# connector-top-j3-1.net
KiCad netlist of a schematic drawn in Altium Designer
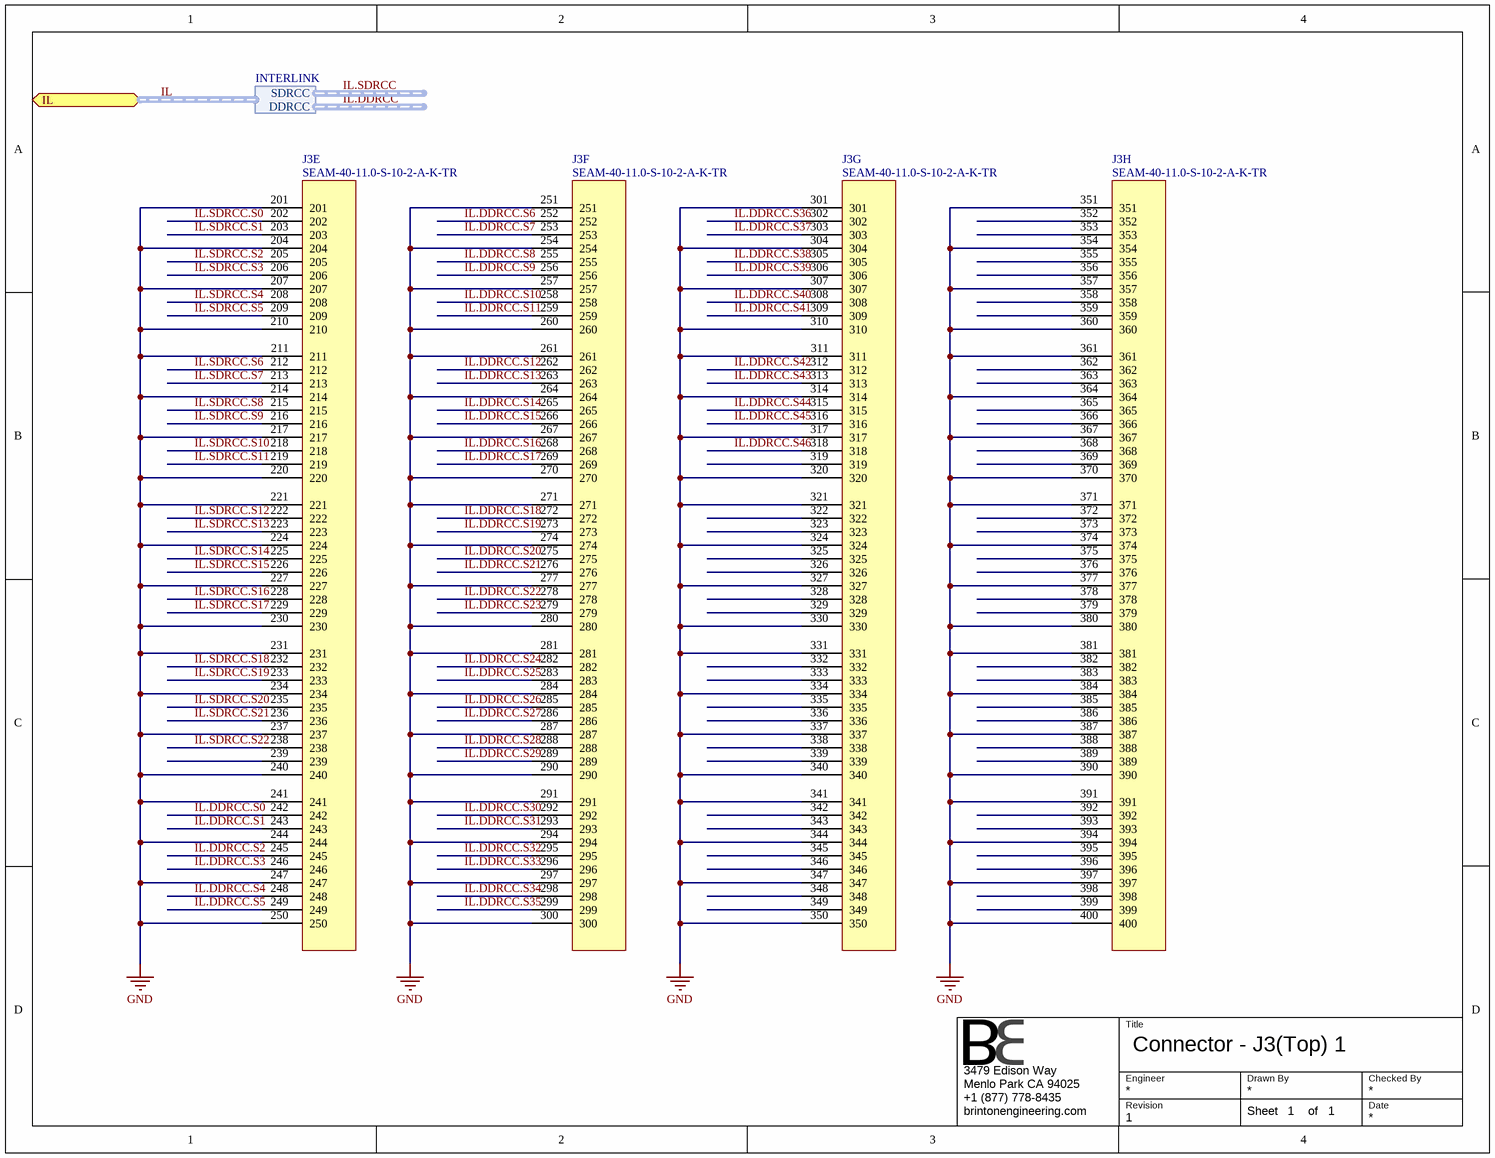
[diagram p0: connector-top-j3-1.SchDoc]

(export (version "E")
  (design (tool "Eeschema 10.0.6"))
  (components
    (comp (ref "J3")
      (value "SEAM-40-11.0-S-10-2-A-K-TR")
      (footprint "samtec:SEAM-40-11.0-S-10-2-A-K-TR")
      (description "Terminal Array Assembly, Surface Mount, 0.050\" Pitch, 400 Pins")
      (fields (field (name "MANUFACTURER") "Samtec"))
      (libsource (lib "samtec") (part "SEAM-40-11.0-S-10-2-A-K-TR"))
    )
  )
  (nets
    (net (code "3") (name "/IL.DDRCC.S0") (class "Default")
      (node (ref "J3") (pin "242") (pinfunction "242_242") (pintype "passive"))
    )
    (net (code "4") (name "/IL.DDRCC.S1") (class "Default")
      (node (ref "J3") (pin "243") (pinfunction "243_243") (pintype "passive"))
    )
    (net (code "5") (name "/IL.DDRCC.S2") (class "Default")
      (node (ref "J3") (pin "245") (pinfunction "245_245") (pintype "passive"))
    )
    (net (code "6") (name "/IL.DDRCC.S3") (class "Default")
      (node (ref "J3") (pin "246") (pinfunction "246_246") (pintype "passive"))
    )
    (net (code "7") (name "/IL.DDRCC.S4") (class "Default")
      (node (ref "J3") (pin "248") (pinfunction "248_248") (pintype "passive"))
    )
    (net (code "8") (name "/IL.DDRCC.S5") (class "Default")
      (node (ref "J3") (pin "249") (pinfunction "249_249") (pintype "passive"))
    )
    (net (code "9") (name "/IL.DDRCC.S6") (class "Default")
      (node (ref "J3") (pin "252") (pinfunction "252_252") (pintype "passive"))
    )
    (net (code "10") (name "/IL.DDRCC.S7") (class "Default")
      (node (ref "J3") (pin "253") (pinfunction "253_253") (pintype "passive"))
    )
    (net (code "11") (name "/IL.DDRCC.S8") (class "Default")
      (node (ref "J3") (pin "255") (pinfunction "255_255") (pintype "passive"))
    )
    (net (code "12") (name "/IL.DDRCC.S9") (class "Default")
      (node (ref "J3") (pin "256") (pinfunction "256_256") (pintype "passive"))
    )
    (net (code "13") (name "/IL.DDRCC.S10") (class "Default")
      (node (ref "J3") (pin "258") (pinfunction "258_258") (pintype "passive"))
    )
    (net (code "14") (name "/IL.DDRCC.S11") (class "Default")
      (node (ref "J3") (pin "259") (pinfunction "259_259") (pintype "passive"))
    )
    (net (code "15") (name "/IL.DDRCC.S12") (class "Default")
      (node (ref "J3") (pin "262") (pinfunction "262_262") (pintype "passive"))
    )
    (net (code "16") (name "/IL.DDRCC.S13") (class "Default")
      (node (ref "J3") (pin "263") (pinfunction "263_263") (pintype "passive"))
    )
    (net (code "17") (name "/IL.DDRCC.S14") (class "Default")
      (node (ref "J3") (pin "265") (pinfunction "265_265") (pintype "passive"))
    )
    (net (code "18") (name "/IL.DDRCC.S15") (class "Default")
      (node (ref "J3") (pin "266") (pinfunction "266_266") (pintype "passive"))
    )
    (net (code "19") (name "/IL.DDRCC.S16") (class "Default")
      (node (ref "J3") (pin "268") (pinfunction "268_268") (pintype "passive"))
    )
    (net (code "20") (name "/IL.DDRCC.S17") (class "Default")
      (node (ref "J3") (pin "269") (pinfunction "269_269") (pintype "passive"))
    )
    (net (code "21") (name "/IL.DDRCC.S18") (class "Default")
      (node (ref "J3") (pin "272") (pinfunction "272_272") (pintype "passive"))
    )
    (net (code "22") (name "/IL.DDRCC.S19") (class "Default")
      (node (ref "J3") (pin "273") (pinfunction "273_273") (pintype "passive"))
    )
    (net (code "23") (name "/IL.DDRCC.S20") (class "Default")
      (node (ref "J3") (pin "275") (pinfunction "275_275") (pintype "passive"))
    )
    (net (code "24") (name "/IL.DDRCC.S21") (class "Default")
      (node (ref "J3") (pin "276") (pinfunction "276_276") (pintype "passive"))
    )
    (net (code "25") (name "/IL.DDRCC.S22") (class "Default")
      (node (ref "J3") (pin "278") (pinfunction "278_278") (pintype "passive"))
    )
    (net (code "26") (name "/IL.DDRCC.S23") (class "Default")
      (node (ref "J3") (pin "279") (pinfunction "279_279") (pintype "passive"))
    )
    (net (code "27") (name "/IL.DDRCC.S24") (class "Default")
      (node (ref "J3") (pin "282") (pinfunction "282_282") (pintype "passive"))
    )
    (net (code "28") (name "/IL.DDRCC.S25") (class "Default")
      (node (ref "J3") (pin "283") (pinfunction "283_283") (pintype "passive"))
    )
    (net (code "29") (name "/IL.DDRCC.S26") (class "Default")
      (node (ref "J3") (pin "285") (pinfunction "285_285") (pintype "passive"))
    )
    (net (code "30") (name "/IL.DDRCC.S27") (class "Default")
      (node (ref "J3") (pin "286") (pinfunction "286_286") (pintype "passive"))
    )
    (net (code "31") (name "/IL.DDRCC.S28") (class "Default")
      (node (ref "J3") (pin "288") (pinfunction "288_288") (pintype "passive"))
    )
    (net (code "32") (name "/IL.DDRCC.S29") (class "Default")
      (node (ref "J3") (pin "289") (pinfunction "289_289") (pintype "passive"))
    )
    (net (code "33") (name "/IL.DDRCC.S30") (class "Default")
      (node (ref "J3") (pin "292") (pinfunction "292_292") (pintype "passive"))
    )
    (net (code "34") (name "/IL.DDRCC.S31") (class "Default")
      (node (ref "J3") (pin "293") (pinfunction "293_293") (pintype "passive"))
    )
    (net (code "35") (name "/IL.DDRCC.S32") (class "Default")
      (node (ref "J3") (pin "295") (pinfunction "295_295") (pintype "passive"))
    )
    (net (code "36") (name "/IL.DDRCC.S33") (class "Default")
      (node (ref "J3") (pin "296") (pinfunction "296_296") (pintype "passive"))
    )
    (net (code "37") (name "/IL.DDRCC.S34") (class "Default")
      (node (ref "J3") (pin "298") (pinfunction "298_298") (pintype "passive"))
    )
    (net (code "38") (name "/IL.DDRCC.S35") (class "Default")
      (node (ref "J3") (pin "299") (pinfunction "299_299") (pintype "passive"))
    )
    (net (code "39") (name "/IL.DDRCC.S36") (class "Default")
      (node (ref "J3") (pin "302") (pinfunction "302_302") (pintype "passive"))
    )
    (net (code "40") (name "/IL.DDRCC.S37") (class "Default")
      (node (ref "J3") (pin "303") (pinfunction "303_303") (pintype "passive"))
    )
    (net (code "41") (name "/IL.DDRCC.S38") (class "Default")
      (node (ref "J3") (pin "305") (pinfunction "305_305") (pintype "passive"))
    )
    (net (code "42") (name "/IL.DDRCC.S39") (class "Default")
      (node (ref "J3") (pin "306") (pinfunction "306_306") (pintype "passive"))
    )
    (net (code "43") (name "/IL.DDRCC.S40") (class "Default")
      (node (ref "J3") (pin "308") (pinfunction "308_308") (pintype "passive"))
    )
    (net (code "44") (name "/IL.DDRCC.S41") (class "Default")
      (node (ref "J3") (pin "309") (pinfunction "309_309") (pintype "passive"))
    )
    (net (code "45") (name "/IL.DDRCC.S42") (class "Default")
      (node (ref "J3") (pin "312") (pinfunction "312_312") (pintype "passive"))
    )
    (net (code "46") (name "/IL.DDRCC.S43") (class "Default")
      (node (ref "J3") (pin "313") (pinfunction "313_313") (pintype "passive"))
    )
    (net (code "47") (name "/IL.DDRCC.S44") (class "Default")
      (node (ref "J3") (pin "315") (pinfunction "315_315") (pintype "passive"))
    )
    (net (code "48") (name "/IL.DDRCC.S45") (class "Default")
      (node (ref "J3") (pin "316") (pinfunction "316_316") (pintype "passive"))
    )
    (net (code "49") (name "/IL.DDRCC.S46") (class "Default")
      (node (ref "J3") (pin "318") (pinfunction "318_318") (pintype "passive"))
    )
    (net (code "51") (name "/IL.SDRCC.S0") (class "Default")
      (node (ref "J3") (pin "202") (pinfunction "202_202") (pintype "passive"))
    )
    (net (code "52") (name "/IL.SDRCC.S1") (class "Default")
      (node (ref "J3") (pin "203") (pinfunction "203_203") (pintype "passive"))
    )
    (net (code "53") (name "/IL.SDRCC.S2") (class "Default")
      (node (ref "J3") (pin "205") (pinfunction "205_205") (pintype "passive"))
    )
    (net (code "54") (name "/IL.SDRCC.S3") (class "Default")
      (node (ref "J3") (pin "206") (pinfunction "206_206") (pintype "passive"))
    )
    (net (code "55") (name "/IL.SDRCC.S4") (class "Default")
      (node (ref "J3") (pin "208") (pinfunction "208_208") (pintype "passive"))
    )
    (net (code "56") (name "/IL.SDRCC.S5") (class "Default")
      (node (ref "J3") (pin "209") (pinfunction "209_209") (pintype "passive"))
    )
    (net (code "57") (name "/IL.SDRCC.S6") (class "Default")
      (node (ref "J3") (pin "212") (pinfunction "212_212") (pintype "passive"))
    )
    (net (code "58") (name "/IL.SDRCC.S7") (class "Default")
      (node (ref "J3") (pin "213") (pinfunction "213_213") (pintype "passive"))
    )
    (net (code "59") (name "/IL.SDRCC.S8") (class "Default")
      (node (ref "J3") (pin "215") (pinfunction "215_215") (pintype "passive"))
    )
    (net (code "60") (name "/IL.SDRCC.S9") (class "Default")
      (node (ref "J3") (pin "216") (pinfunction "216_216") (pintype "passive"))
    )
    (net (code "61") (name "/IL.SDRCC.S10") (class "Default")
      (node (ref "J3") (pin "218") (pinfunction "218_218") (pintype "passive"))
    )
    (net (code "62") (name "/IL.SDRCC.S11") (class "Default")
      (node (ref "J3") (pin "219") (pinfunction "219_219") (pintype "passive"))
    )
    (net (code "63") (name "/IL.SDRCC.S12") (class "Default")
      (node (ref "J3") (pin "222") (pinfunction "222_222") (pintype "passive"))
    )
    (net (code "64") (name "/IL.SDRCC.S13") (class "Default")
      (node (ref "J3") (pin "223") (pinfunction "223_223") (pintype "passive"))
    )
    (net (code "65") (name "/IL.SDRCC.S14") (class "Default")
      (node (ref "J3") (pin "225") (pinfunction "225_225") (pintype "passive"))
    )
    (net (code "66") (name "/IL.SDRCC.S15") (class "Default")
      (node (ref "J3") (pin "226") (pinfunction "226_226") (pintype "passive"))
    )
    (net (code "67") (name "/IL.SDRCC.S16") (class "Default")
      (node (ref "J3") (pin "228") (pinfunction "228_228") (pintype "passive"))
    )
    (net (code "68") (name "/IL.SDRCC.S17") (class "Default")
      (node (ref "J3") (pin "229") (pinfunction "229_229") (pintype "passive"))
    )
    (net (code "69") (name "/IL.SDRCC.S18") (class "Default")
      (node (ref "J3") (pin "232") (pinfunction "232_232") (pintype "passive"))
    )
    (net (code "70") (name "/IL.SDRCC.S19") (class "Default")
      (node (ref "J3") (pin "233") (pinfunction "233_233") (pintype "passive"))
    )
    (net (code "71") (name "/IL.SDRCC.S20") (class "Default")
      (node (ref "J3") (pin "235") (pinfunction "235_235") (pintype "passive"))
    )
    (net (code "72") (name "/IL.SDRCC.S21") (class "Default")
      (node (ref "J3") (pin "236") (pinfunction "236_236") (pintype "passive"))
    )
    (net (code "73") (name "/IL.SDRCC.S22") (class "Default")
      (node (ref "J3") (pin "238") (pinfunction "238_238") (pintype "passive"))
    )
    (net (code "75") (name "GND") (class "Default")
      (node (ref "J3") (pin "201") (pinfunction "201_201") (pintype "passive"))
      (node (ref "J3") (pin "204") (pinfunction "204_204") (pintype "passive"))
      (node (ref "J3") (pin "207") (pinfunction "207_207") (pintype "passive"))
      (node (ref "J3") (pin "210") (pinfunction "210_210") (pintype "passive"))
      (node (ref "J3") (pin "211") (pinfunction "211_211") (pintype "passive"))
      (node (ref "J3") (pin "214") (pinfunction "214_214") (pintype "passive"))
      (node (ref "J3") (pin "217") (pinfunction "217_217") (pintype "passive"))
      (node (ref "J3") (pin "220") (pinfunction "220_220") (pintype "passive"))
      (node (ref "J3") (pin "221") (pinfunction "221_221") (pintype "passive"))
      (node (ref "J3") (pin "224") (pinfunction "224_224") (pintype "passive"))
      (node (ref "J3") (pin "227") (pinfunction "227_227") (pintype "passive"))
      (node (ref "J3") (pin "230") (pinfunction "230_230") (pintype "passive"))
      (node (ref "J3") (pin "231") (pinfunction "231_231") (pintype "passive"))
      (node (ref "J3") (pin "234") (pinfunction "234_234") (pintype "passive"))
      (node (ref "J3") (pin "237") (pinfunction "237_237") (pintype "passive"))
      (node (ref "J3") (pin "240") (pinfunction "240_240") (pintype "passive"))
      (node (ref "J3") (pin "241") (pinfunction "241_241") (pintype "passive"))
      (node (ref "J3") (pin "244") (pinfunction "244_244") (pintype "passive"))
      (node (ref "J3") (pin "247") (pinfunction "247_247") (pintype "passive"))
      (node (ref "J3") (pin "250") (pinfunction "250_250") (pintype "passive"))
      (node (ref "J3") (pin "251") (pinfunction "251_251") (pintype "passive"))
      (node (ref "J3") (pin "254") (pinfunction "254_254") (pintype "passive"))
      (node (ref "J3") (pin "257") (pinfunction "257_257") (pintype "passive"))
      (node (ref "J3") (pin "260") (pinfunction "260_260") (pintype "passive"))
      (node (ref "J3") (pin "261") (pinfunction "261_261") (pintype "passive"))
      (node (ref "J3") (pin "264") (pinfunction "264_264") (pintype "passive"))
      (node (ref "J3") (pin "267") (pinfunction "267_267") (pintype "passive"))
      (node (ref "J3") (pin "270") (pinfunction "270_270") (pintype "passive"))
      (node (ref "J3") (pin "271") (pinfunction "271_271") (pintype "passive"))
      (node (ref "J3") (pin "274") (pinfunction "274_274") (pintype "passive"))
      (node (ref "J3") (pin "277") (pinfunction "277_277") (pintype "passive"))
      (node (ref "J3") (pin "280") (pinfunction "280_280") (pintype "passive"))
      (node (ref "J3") (pin "281") (pinfunction "281_281") (pintype "passive"))
      (node (ref "J3") (pin "284") (pinfunction "284_284") (pintype "passive"))
      (node (ref "J3") (pin "287") (pinfunction "287_287") (pintype "passive"))
      (node (ref "J3") (pin "290") (pinfunction "290_290") (pintype "passive"))
      (node (ref "J3") (pin "291") (pinfunction "291_291") (pintype "passive"))
      (node (ref "J3") (pin "294") (pinfunction "294_294") (pintype "passive"))
      (node (ref "J3") (pin "297") (pinfunction "297_297") (pintype "passive"))
      (node (ref "J3") (pin "300") (pinfunction "300_300") (pintype "passive"))
      (node (ref "J3") (pin "301") (pinfunction "301_301") (pintype "passive"))
      (node (ref "J3") (pin "304") (pinfunction "304_304") (pintype "passive"))
      (node (ref "J3") (pin "307") (pinfunction "307_307") (pintype "passive"))
      (node (ref "J3") (pin "310") (pinfunction "310_310") (pintype "passive"))
      (node (ref "J3") (pin "311") (pinfunction "311_311") (pintype "passive"))
      (node (ref "J3") (pin "314") (pinfunction "314_314") (pintype "passive"))
      (node (ref "J3") (pin "317") (pinfunction "317_317") (pintype "passive"))
      (node (ref "J3") (pin "320") (pinfunction "320_320") (pintype "passive"))
      (node (ref "J3") (pin "321") (pinfunction "321_321") (pintype "passive"))
      (node (ref "J3") (pin "324") (pinfunction "324_324") (pintype "passive"))
      (node (ref "J3") (pin "327") (pinfunction "327_327") (pintype "passive"))
      (node (ref "J3") (pin "330") (pinfunction "330_330") (pintype "passive"))
      (node (ref "J3") (pin "331") (pinfunction "331_331") (pintype "passive"))
      (node (ref "J3") (pin "334") (pinfunction "334_334") (pintype "passive"))
      (node (ref "J3") (pin "337") (pinfunction "337_337") (pintype "passive"))
      (node (ref "J3") (pin "340") (pinfunction "340_340") (pintype "passive"))
      (node (ref "J3") (pin "341") (pinfunction "341_341") (pintype "passive"))
      (node (ref "J3") (pin "344") (pinfunction "344_344") (pintype "passive"))
      (node (ref "J3") (pin "347") (pinfunction "347_347") (pintype "passive"))
      (node (ref "J3") (pin "350") (pinfunction "350_350") (pintype "passive"))
      (node (ref "J3") (pin "351") (pinfunction "351_351") (pintype "passive"))
      (node (ref "J3") (pin "354") (pinfunction "354_354") (pintype "passive"))
      (node (ref "J3") (pin "357") (pinfunction "357_357") (pintype "passive"))
      (node (ref "J3") (pin "360") (pinfunction "360_360") (pintype "passive"))
      (node (ref "J3") (pin "361") (pinfunction "361_361") (pintype "passive"))
      (node (ref "J3") (pin "364") (pinfunction "364_364") (pintype "passive"))
      (node (ref "J3") (pin "367") (pinfunction "367_367") (pintype "passive"))
      (node (ref "J3") (pin "370") (pinfunction "370_370") (pintype "passive"))
      (node (ref "J3") (pin "371") (pinfunction "371_371") (pintype "passive"))
      (node (ref "J3") (pin "374") (pinfunction "374_374") (pintype "passive"))
      (node (ref "J3") (pin "377") (pinfunction "377_377") (pintype "passive"))
      (node (ref "J3") (pin "380") (pinfunction "380_380") (pintype "passive"))
      (node (ref "J3") (pin "381") (pinfunction "381_381") (pintype "passive"))
      (node (ref "J3") (pin "384") (pinfunction "384_384") (pintype "passive"))
      (node (ref "J3") (pin "387") (pinfunction "387_387") (pintype "passive"))
      (node (ref "J3") (pin "390") (pinfunction "390_390") (pintype "passive"))
      (node (ref "J3") (pin "391") (pinfunction "391_391") (pintype "passive"))
      (node (ref "J3") (pin "394") (pinfunction "394_394") (pintype "passive"))
      (node (ref "J3") (pin "397") (pinfunction "397_397") (pintype "passive"))
      (node (ref "J3") (pin "400") (pinfunction "400_400") (pintype "passive"))
    )
    (net (code "76") (name "unconnected-(J3-Pad239)") (class "Default")
      (node (ref "J3") (pin "239") (pinfunction "239_239") (pintype "passive"))
    )
    (net (code "77") (name "unconnected-(J3-Pad319)") (class "Default")
      (node (ref "J3") (pin "319") (pinfunction "319_319") (pintype "passive"))
    )
    (net (code "78") (name "unconnected-(J3-Pad322)") (class "Default")
      (node (ref "J3") (pin "322") (pinfunction "322_322") (pintype "passive"))
    )
    (net (code "79") (name "unconnected-(J3-Pad323)") (class "Default")
      (node (ref "J3") (pin "323") (pinfunction "323_323") (pintype "passive"))
    )
    (net (code "80") (name "unconnected-(J3-Pad325)") (class "Default")
      (node (ref "J3") (pin "325") (pinfunction "325_325") (pintype "passive"))
    )
    (net (code "81") (name "unconnected-(J3-Pad326)") (class "Default")
      (node (ref "J3") (pin "326") (pinfunction "326_326") (pintype "passive"))
    )
    (net (code "82") (name "unconnected-(J3-Pad328)") (class "Default")
      (node (ref "J3") (pin "328") (pinfunction "328_328") (pintype "passive"))
    )
    (net (code "83") (name "unconnected-(J3-Pad329)") (class "Default")
      (node (ref "J3") (pin "329") (pinfunction "329_329") (pintype "passive"))
    )
    (net (code "84") (name "unconnected-(J3-Pad332)") (class "Default")
      (node (ref "J3") (pin "332") (pinfunction "332_332") (pintype "passive"))
    )
    (net (code "85") (name "unconnected-(J3-Pad333)") (class "Default")
      (node (ref "J3") (pin "333") (pinfunction "333_333") (pintype "passive"))
    )
    (net (code "86") (name "unconnected-(J3-Pad335)") (class "Default")
      (node (ref "J3") (pin "335") (pinfunction "335_335") (pintype "passive"))
    )
    (net (code "87") (name "unconnected-(J3-Pad336)") (class "Default")
      (node (ref "J3") (pin "336") (pinfunction "336_336") (pintype "passive"))
    )
    (net (code "88") (name "unconnected-(J3-Pad338)") (class "Default")
      (node (ref "J3") (pin "338") (pinfunction "338_338") (pintype "passive"))
    )
    (net (code "89") (name "unconnected-(J3-Pad339)") (class "Default")
      (node (ref "J3") (pin "339") (pinfunction "339_339") (pintype "passive"))
    )
    (net (code "90") (name "unconnected-(J3-Pad342)") (class "Default")
      (node (ref "J3") (pin "342") (pinfunction "342_342") (pintype "passive"))
    )
    (net (code "91") (name "unconnected-(J3-Pad343)") (class "Default")
      (node (ref "J3") (pin "343") (pinfunction "343_343") (pintype "passive"))
    )
    (net (code "92") (name "unconnected-(J3-Pad345)") (class "Default")
      (node (ref "J3") (pin "345") (pinfunction "345_345") (pintype "passive"))
    )
    (net (code "93") (name "unconnected-(J3-Pad346)") (class "Default")
      (node (ref "J3") (pin "346") (pinfunction "346_346") (pintype "passive"))
    )
    (net (code "94") (name "unconnected-(J3-Pad348)") (class "Default")
      (node (ref "J3") (pin "348") (pinfunction "348_348") (pintype "passive"))
    )
    (net (code "95") (name "unconnected-(J3-Pad349)") (class "Default")
      (node (ref "J3") (pin "349") (pinfunction "349_349") (pintype "passive"))
    )
    (net (code "96") (name "unconnected-(J3-Pad352)") (class "Default")
      (node (ref "J3") (pin "352") (pinfunction "352_352") (pintype "passive"))
    )
    (net (code "97") (name "unconnected-(J3-Pad353)") (class "Default")
      (node (ref "J3") (pin "353") (pinfunction "353_353") (pintype "passive"))
    )
    (net (code "98") (name "unconnected-(J3-Pad355)") (class "Default")
      (node (ref "J3") (pin "355") (pinfunction "355_355") (pintype "passive"))
    )
    (net (code "99") (name "unconnected-(J3-Pad356)") (class "Default")
      (node (ref "J3") (pin "356") (pinfunction "356_356") (pintype "passive"))
    )
    (net (code "100") (name "unconnected-(J3-Pad358)") (class "Default")
      (node (ref "J3") (pin "358") (pinfunction "358_358") (pintype "passive"))
    )
    (net (code "101") (name "unconnected-(J3-Pad359)") (class "Default")
      (node (ref "J3") (pin "359") (pinfunction "359_359") (pintype "passive"))
    )
    (net (code "102") (name "unconnected-(J3-Pad362)") (class "Default")
      (node (ref "J3") (pin "362") (pinfunction "362_362") (pintype "passive"))
    )
    (net (code "103") (name "unconnected-(J3-Pad363)") (class "Default")
      (node (ref "J3") (pin "363") (pinfunction "363_363") (pintype "passive"))
    )
    (net (code "104") (name "unconnected-(J3-Pad365)") (class "Default")
      (node (ref "J3") (pin "365") (pinfunction "365_365") (pintype "passive"))
    )
    (net (code "105") (name "unconnected-(J3-Pad366)") (class "Default")
      (node (ref "J3") (pin "366") (pinfunction "366_366") (pintype "passive"))
    )
    (net (code "106") (name "unconnected-(J3-Pad368)") (class "Default")
      (node (ref "J3") (pin "368") (pinfunction "368_368") (pintype "passive"))
    )
    (net (code "107") (name "unconnected-(J3-Pad369)") (class "Default")
      (node (ref "J3") (pin "369") (pinfunction "369_369") (pintype "passive"))
    )
    (net (code "108") (name "unconnected-(J3-Pad372)") (class "Default")
      (node (ref "J3") (pin "372") (pinfunction "372_372") (pintype "passive"))
    )
    (net (code "109") (name "unconnected-(J3-Pad373)") (class "Default")
      (node (ref "J3") (pin "373") (pinfunction "373_373") (pintype "passive"))
    )
    (net (code "110") (name "unconnected-(J3-Pad375)") (class "Default")
      (node (ref "J3") (pin "375") (pinfunction "375_375") (pintype "passive"))
    )
    (net (code "111") (name "unconnected-(J3-Pad376)") (class "Default")
      (node (ref "J3") (pin "376") (pinfunction "376_376") (pintype "passive"))
    )
    (net (code "112") (name "unconnected-(J3-Pad378)") (class "Default")
      (node (ref "J3") (pin "378") (pinfunction "378_378") (pintype "passive"))
    )
    (net (code "113") (name "unconnected-(J3-Pad379)") (class "Default")
      (node (ref "J3") (pin "379") (pinfunction "379_379") (pintype "passive"))
    )
    (net (code "114") (name "unconnected-(J3-Pad382)") (class "Default")
      (node (ref "J3") (pin "382") (pinfunction "382_382") (pintype "passive"))
    )
    (net (code "115") (name "unconnected-(J3-Pad383)") (class "Default")
      (node (ref "J3") (pin "383") (pinfunction "383_383") (pintype "passive"))
    )
    (net (code "116") (name "unconnected-(J3-Pad385)") (class "Default")
      (node (ref "J3") (pin "385") (pinfunction "385_385") (pintype "passive"))
    )
    (net (code "117") (name "unconnected-(J3-Pad386)") (class "Default")
      (node (ref "J3") (pin "386") (pinfunction "386_386") (pintype "passive"))
    )
    (net (code "118") (name "unconnected-(J3-Pad388)") (class "Default")
      (node (ref "J3") (pin "388") (pinfunction "388_388") (pintype "passive"))
    )
    (net (code "119") (name "unconnected-(J3-Pad389)") (class "Default")
      (node (ref "J3") (pin "389") (pinfunction "389_389") (pintype "passive"))
    )
    (net (code "120") (name "unconnected-(J3-Pad392)") (class "Default")
      (node (ref "J3") (pin "392") (pinfunction "392_392") (pintype "passive"))
    )
    (net (code "121") (name "unconnected-(J3-Pad393)") (class "Default")
      (node (ref "J3") (pin "393") (pinfunction "393_393") (pintype "passive"))
    )
    (net (code "122") (name "unconnected-(J3-Pad395)") (class "Default")
      (node (ref "J3") (pin "395") (pinfunction "395_395") (pintype "passive"))
    )
    (net (code "123") (name "unconnected-(J3-Pad396)") (class "Default")
      (node (ref "J3") (pin "396") (pinfunction "396_396") (pintype "passive"))
    )
    (net (code "124") (name "unconnected-(J3-Pad398)") (class "Default")
      (node (ref "J3") (pin "398") (pinfunction "398_398") (pintype "passive"))
    )
    (net (code "125") (name "unconnected-(J3-Pad399)") (class "Default")
      (node (ref "J3") (pin "399") (pinfunction "399_399") (pintype "passive"))
    )
  )
)
